# uven2-mk3-lid-switch-A.net
KiCad netlist of a schematic drawn in EasyEDA Pro
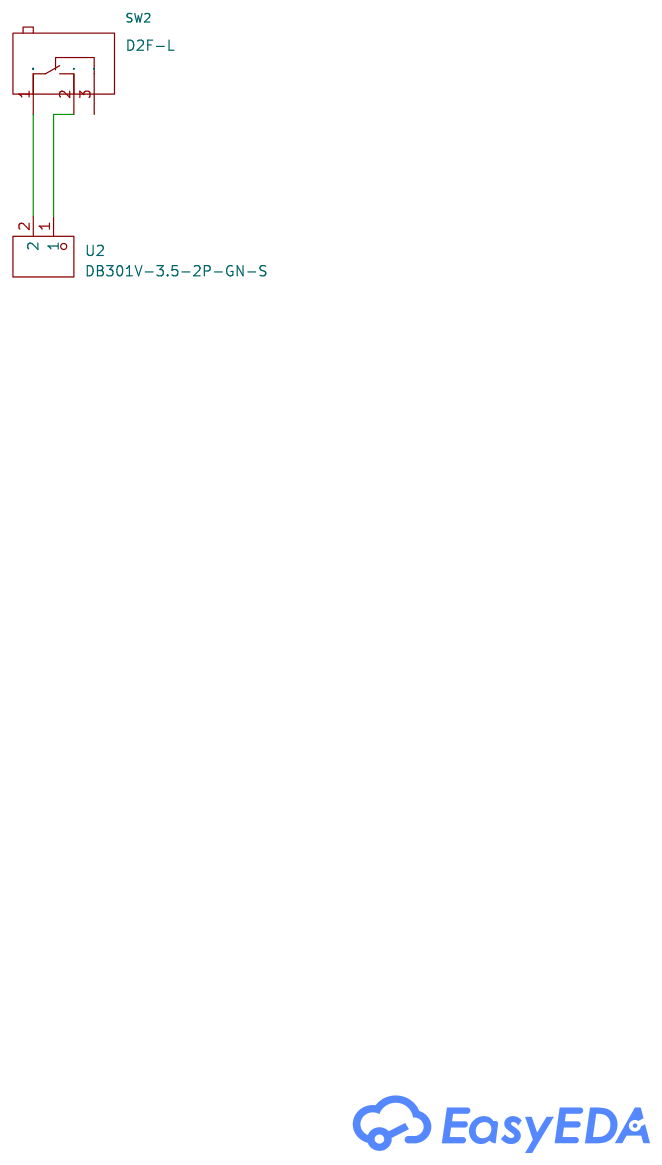
[diagram p0: schematic sheet]

(export (version "E")
  (design (tool "Eeschema 10.0.6"))
  (components
    (comp (ref "SW2")
      (value "D2F-L")
      (footprint "easyedapro:SW-TH_D2F-L")
      (fields (field (name "Manufacturer") "OMRON(欧姆龙)"))
      (libsource (lib "easyedapro") (part "D2F-L"))
    )
    (comp (ref "U2")
      (value "DB301V-3.5-2P-GN-S")
      (footprint "easyedapro:CONN-TH_DB301V-3.5-2P-GN")
      (fields (field (name "Manufacturer") "DORABO(地博电气)"))
      (libsource (lib "easyedapro") (part "DB301V-3.5-2P-GN"))
    )
  )
  (nets
    (net (code "1") (name "Net-(SW2-COM)") (class "Default")
      (node (ref "SW2") (pin "1") (pinfunction "COM_1") (pintype "input"))
      (node (ref "U2") (pin "2") (pinfunction "2_2") (pintype "unspecified"))
    )
    (net (code "2") (name "Net-(SW2-NO)") (class "Default")
      (node (ref "SW2") (pin "2") (pinfunction "NO_2") (pintype "input"))
      (node (ref "U2") (pin "1") (pinfunction "1_1") (pintype "unspecified"))
    )
    (net (code "3") (name "unconnected-(SW2-NC-Pad3)") (class "Default")
      (node (ref "SW2") (pin "3") (pinfunction "NC_3") (pintype "input"))
    )
  )
)
